# Puzzle_Chainable_RGB_LED.net
KiCad netlist of a schematic drawn in EAGLE
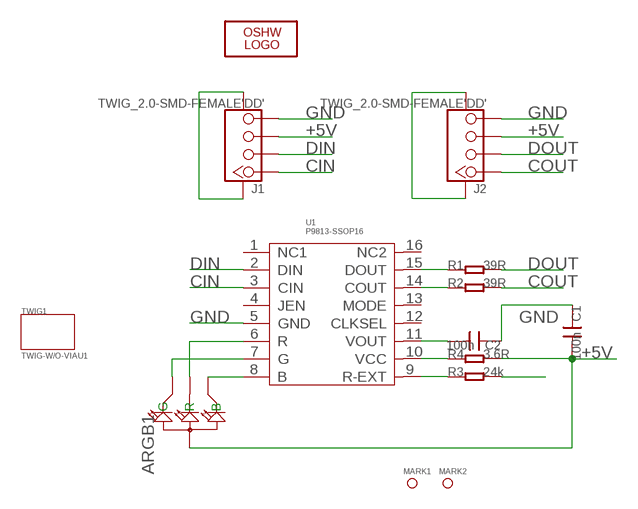
[diagram p0: schematic, sheet 1]

(export (version "E")
  (design (tool "Eeschema 10.0.6"))
  (components
    (comp (ref "ARGB1")
      (value "LED-ARGB-DIP2.0")
      (footprint "eagle-import:ARGB_2.0")
      (libsource (lib "eagle-import") (part "LED-ARGB-DIP2.0"))
    )
    (comp (ref "C1")
      (value "100n")
      (footprint "eagle-import:0603")
      (libsource (lib "eagle-import") (part "C-0603"))
    )
    (comp (ref "C2")
      (value "100n")
      (footprint "eagle-import:0603")
      (libsource (lib "eagle-import") (part "C-0603"))
    )
    (comp (ref "J1")
      (value "TWIG_2.0-SMD-FEMALE'DD'")
      (footprint "eagle-import:2.0_1X4DD")
      (libsource (lib "eagle-import") (part "TWIG_2.0-SMD-FEMALE'DD'"))
    )
    (comp (ref "J2")
      (value "TWIG_2.0-SMD-FEMALE'DD'")
      (footprint "eagle-import:2.0_1X4DD")
      (libsource (lib "eagle-import") (part "TWIG_2.0-SMD-FEMALE'DD'"))
    )
    (comp (ref "LOGO1")
      (value "LOGO-OSHW-FILLX0100-NT")
      (footprint "eagle-import:OSHW_FILLX100_NOTEXT")
      (libsource (lib "eagle-import") (part "LOGO-OSHW-FILLX0100-NT"))
    )
    (comp (ref "MARK1")
      (value "PAD-MARK")
      (footprint "eagle-import:MARK")
      (libsource (lib "eagle-import") (part "PAD-MARK"))
    )
    (comp (ref "MARK2")
      (value "PAD-MARK")
      (footprint "eagle-import:MARK")
      (libsource (lib "eagle-import") (part "PAD-MARK"))
    )
    (comp (ref "R1")
      (value "39R")
      (footprint "eagle-import:0603")
      (libsource (lib "eagle-import") (part "R-0603"))
    )
    (comp (ref "R2")
      (value "39R")
      (footprint "eagle-import:0603")
      (libsource (lib "eagle-import") (part "R-0603"))
    )
    (comp (ref "R3")
      (value "24k")
      (footprint "eagle-import:0603")
      (libsource (lib "eagle-import") (part "R-0603"))
    )
    (comp (ref "R4")
      (value "3.6R")
      (footprint "eagle-import:0603")
      (libsource (lib "eagle-import") (part "R-0603"))
    )
    (comp (ref "TWIG1")
      (value "TWIG-W/O-VIAU1")
      (footprint "eagle-import:U1N")
      (libsource (lib "eagle-import") (part "TWIG-W/O-VIAU1"))
    )
    (comp (ref "U1")
      (value "P9813-SSOP16")
      (footprint "eagle-import:SSOP16")
      (libsource (lib "eagle-import") (part "P9813-SSOP16"))
    )
  )
  (nets
    (net (code "1") (name "/+5V") (class "Default")
      (node (ref "ARGB1") (pin "2") (pinfunction "+_2") (pintype "bidirectional"))
      (node (ref "C1") (pin "2") (pinfunction "2_2") (pintype "passive"))
      (node (ref "J1") (pin "3") (pinfunction "3_3") (pintype "bidirectional"))
      (node (ref "J2") (pin "3") (pinfunction "3_3") (pintype "bidirectional"))
      (node (ref "R4") (pin "2") (pinfunction "2_2") (pintype "passive"))
    )
    (net (code "2") (name "/CIN") (class "Default")
      (node (ref "J1") (pin "1") (pinfunction "1_1") (pintype "bidirectional"))
      (node (ref "U1") (pin "3") (pinfunction "CIN_3") (pintype "input"))
    )
    (net (code "3") (name "/COUT") (class "Default")
      (node (ref "J2") (pin "1") (pinfunction "1_1") (pintype "bidirectional"))
      (node (ref "R2") (pin "2") (pinfunction "2_2") (pintype "passive"))
    )
    (net (code "4") (name "/DIN") (class "Default")
      (node (ref "J1") (pin "2") (pinfunction "2_2") (pintype "bidirectional"))
      (node (ref "U1") (pin "2") (pinfunction "DIN_2") (pintype "input"))
    )
    (net (code "5") (name "/DOUT") (class "Default")
      (node (ref "J2") (pin "2") (pinfunction "2_2") (pintype "bidirectional"))
      (node (ref "R1") (pin "2") (pinfunction "2_2") (pintype "passive"))
    )
    (net (code "6") (name "/GND") (class "Default")
      (node (ref "C1") (pin "1") (pinfunction "1_1") (pintype "passive"))
      (node (ref "C2") (pin "1") (pinfunction "1_1") (pintype "passive"))
      (node (ref "J1") (pin "4") (pinfunction "4_4") (pintype "bidirectional"))
      (node (ref "J1") (pin "SS1") (pinfunction "SS1_SS1") (pintype "bidirectional"))
      (node (ref "J1") (pin "SS2") (pinfunction "SS2_SS2") (pintype "bidirectional"))
      (node (ref "J2") (pin "4") (pinfunction "4_4") (pintype "bidirectional"))
      (node (ref "J2") (pin "SS1") (pinfunction "SS1_SS1") (pintype "bidirectional"))
      (node (ref "J2") (pin "SS2") (pinfunction "SS2_SS2") (pintype "bidirectional"))
      (node (ref "R3") (pin "2") (pinfunction "2_2") (pintype "passive"))
      (node (ref "U1") (pin "5") (pinfunction "GND_5") (pintype "power_in"))
    )
    (net (code "7") (name "Net-(ARGB1-B)") (class "Default")
      (node (ref "ARGB1") (pin "4") (pinfunction "B_4") (pintype "bidirectional"))
      (node (ref "U1") (pin "8") (pinfunction "B_8") (pintype "output"))
    )
    (net (code "8") (name "Net-(ARGB1-G)") (class "Default")
      (node (ref "ARGB1") (pin "3") (pinfunction "G_3") (pintype "bidirectional"))
      (node (ref "U1") (pin "7") (pinfunction "G_7") (pintype "output"))
    )
    (net (code "9") (name "Net-(ARGB1-R)") (class "Default")
      (node (ref "ARGB1") (pin "1") (pinfunction "R_1") (pintype "bidirectional"))
      (node (ref "U1") (pin "6") (pinfunction "R_6") (pintype "output"))
    )
    (net (code "10") (name "Net-(U1-COUT)") (class "Default")
      (node (ref "R2") (pin "1") (pinfunction "1_1") (pintype "passive"))
      (node (ref "U1") (pin "14") (pinfunction "COUT_14") (pintype "output"))
    )
    (net (code "11") (name "Net-(U1-DOUT)") (class "Default")
      (node (ref "R1") (pin "1") (pinfunction "1_1") (pintype "passive"))
      (node (ref "U1") (pin "15") (pinfunction "DOUT_15") (pintype "output"))
    )
    (net (code "12") (name "Net-(U1-R-EXT)") (class "Default")
      (node (ref "R3") (pin "1") (pinfunction "1_1") (pintype "passive"))
      (node (ref "U1") (pin "9") (pinfunction "R-EXT_9") (pintype "input"))
    )
    (net (code "13") (name "Net-(U1-VCC)") (class "Default")
      (node (ref "R4") (pin "1") (pinfunction "1_1") (pintype "passive"))
      (node (ref "U1") (pin "10") (pinfunction "VCC_10") (pintype "power_in"))
    )
    (net (code "14") (name "Net-(U1-VOUT)") (class "Default")
      (node (ref "C2") (pin "2") (pinfunction "2_2") (pintype "passive"))
      (node (ref "U1") (pin "11") (pinfunction "VOUT_11") (pintype "output"))
    )
    (net (code "15") (name "unconnected-(U1-CLKSEL-Pad12)") (class "Default")
      (node (ref "U1") (pin "12") (pinfunction "CLKSEL_12") (pintype "input"))
    )
    (net (code "16") (name "unconnected-(U1-JEN-Pad4)") (class "Default")
      (node (ref "U1") (pin "4") (pinfunction "JEN_4") (pintype "input"))
    )
    (net (code "17") (name "unconnected-(U1-MODE-Pad13)") (class "Default")
      (node (ref "U1") (pin "13") (pinfunction "MODE_13") (pintype "input"))
    )
    (net (code "18") (name "unconnected-(U1-NC1-Pad1)") (class "Default")
      (node (ref "U1") (pin "1") (pinfunction "NC1_1") (pintype "no_connect"))
    )
    (net (code "19") (name "unconnected-(U1-NC2-Pad16)") (class "Default")
      (node (ref "U1") (pin "16") (pinfunction "NC2_16") (pintype "no_connect"))
    )
  )
)
